# car_in.net
KiCad netlist of a schematic drawn in Altium Designer
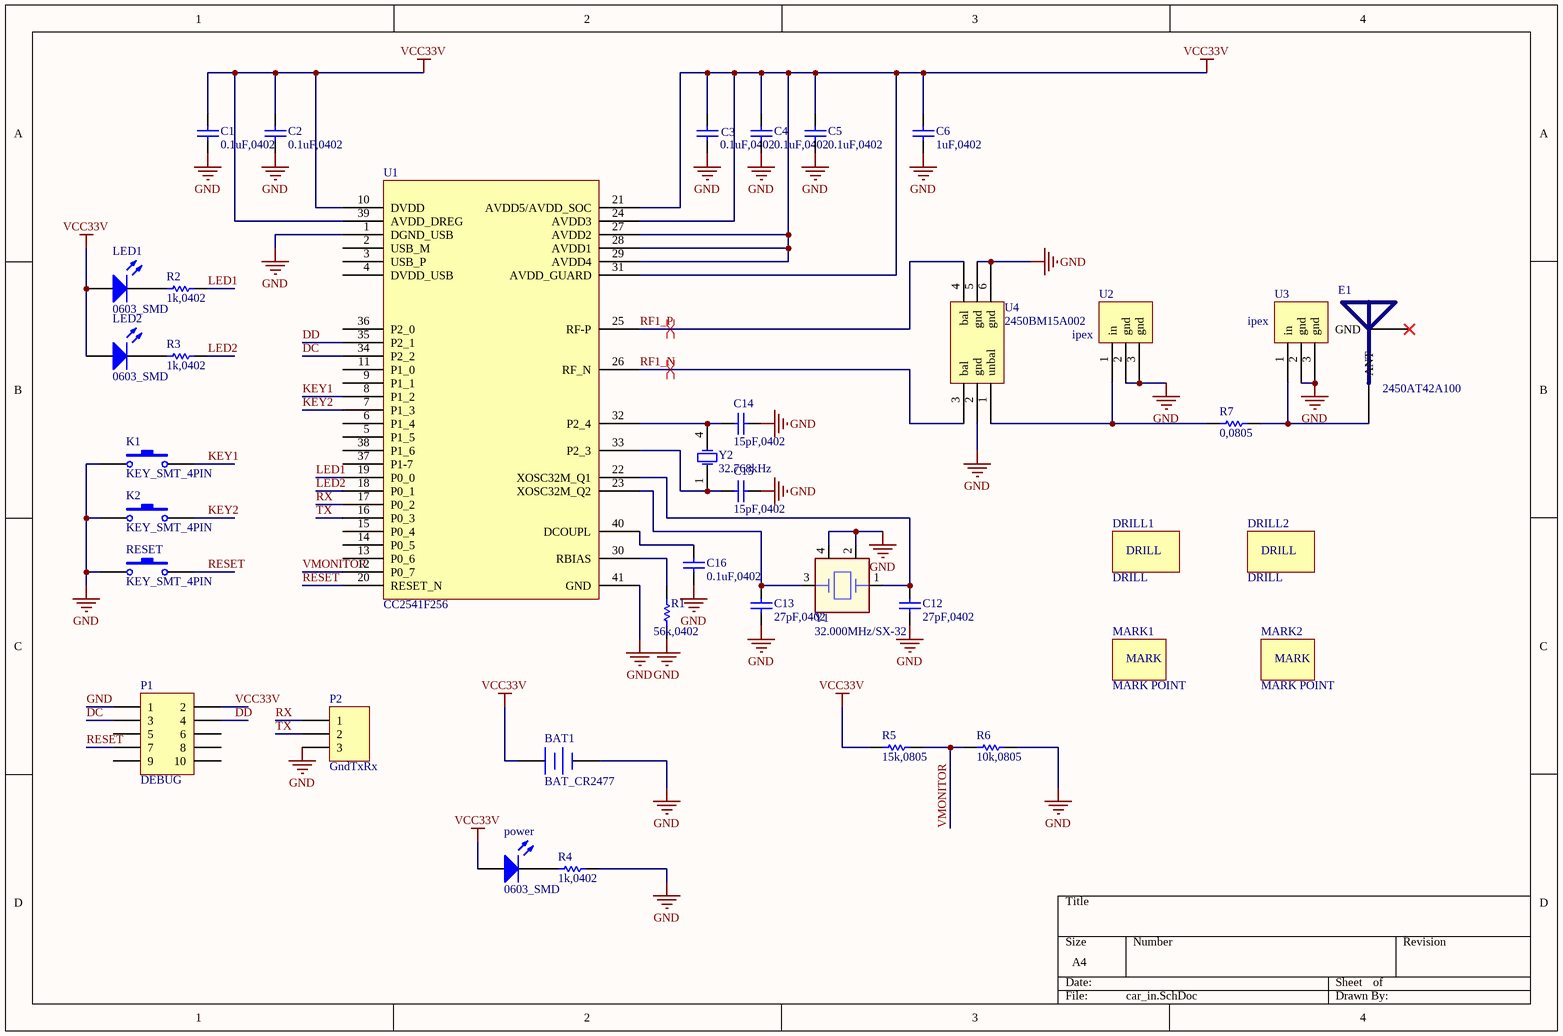
[diagram p0: car_in.SchDoc]

(export (version "E")
  (design (tool "Eeschema 10.0.6"))
  (components
    (comp (ref "BAT1")
      (value "BAT_CR2477")
      (footprint "CR2477")
      (description "battery")
      (libsource (lib "Inte") (part "BAT"))
    )
    (comp (ref "C1")
      (value "0.1uF,0402")
      (footprint "C0402")
      (description "Capacitor")
      (fields (field (name "PUBLISHER") "Altium Limited"))
      (libsource (lib "Inte") (part "CAP"))
    )
    (comp (ref "C2")
      (value "0.1uF,0402")
      (footprint "C0402")
      (description "Capacitor")
      (fields (field (name "PUBLISHER") "Altium Limited"))
      (libsource (lib "Inte") (part "CAP"))
    )
    (comp (ref "C3")
      (value "0.1uF,0402")
      (footprint "C0402")
      (description "Capacitor")
      (fields (field (name "PUBLISHER") "Altium Limited"))
      (libsource (lib "Inte") (part "CAP"))
    )
    (comp (ref "C4")
      (value "0.1uF,0402")
      (footprint "C0402")
      (description "Capacitor")
      (fields (field (name "PUBLISHER") "Altium Limited"))
      (libsource (lib "Inte") (part "CAP"))
    )
    (comp (ref "C5")
      (value "0.1uF,0402")
      (footprint "C0402")
      (description "Capacitor")
      (fields (field (name "PUBLISHER") "Altium Limited"))
      (libsource (lib "Inte") (part "CAP"))
    )
    (comp (ref "C6")
      (value "1uF,0402")
      (footprint "C0402")
      (description "Capacitor")
      (fields (field (name "PUBLISHER") "Altium Limited"))
      (libsource (lib "Inte") (part "CAP"))
    )
    (comp (ref "C12")
      (value "27pF,0402")
      (footprint "C0402")
      (description "Capacitor")
      (fields (field (name "PUBLISHER") "Altium Limited"))
      (libsource (lib "Inte") (part "CAP"))
    )
    (comp (ref "C13")
      (value "27pF,0402")
      (footprint "C0402")
      (description "Capacitor")
      (fields (field (name "PUBLISHER") "Altium Limited"))
      (libsource (lib "Inte") (part "CAP"))
    )
    (comp (ref "C14")
      (value "15pF,0402")
      (footprint "C0402")
      (description "Capacitor")
      (fields (field (name "PUBLISHER") "Altium Limited"))
      (libsource (lib "Inte") (part "CAP"))
    )
    (comp (ref "C15")
      (value "15pF,0402")
      (footprint "C0402")
      (description "Capacitor")
      (fields (field (name "PUBLISHER") "Altium Limited"))
      (libsource (lib "Inte") (part "CAP"))
    )
    (comp (ref "C16")
      (value "0.1uF,0402")
      (footprint "C0402")
      (description "Capacitor")
      (fields (field (name "PUBLISHER") "Altium Limited"))
      (libsource (lib "Inte") (part "CAP"))
    )
    (comp (ref "DRILL1") (value "DRILL") (footprint "DRILL_2MM") (libsource (lib "Inte") (part "DRILL")))
    (comp (ref "DRILL2") (value "DRILL") (footprint "DRILL_2MM") (libsource (lib "Inte") (part "DRILL")))
    (comp (ref "E1")
      (value "2450AT42A100")
      (footprint "BT_ANT_PCB")
      (libsource (lib "Inte") (part "BT_ANT_PCB"))
    )
    (comp (ref "K1") (value "KEY_SMT_4PIN") (footprint "KEY-SMT") (libsource (lib "Inte") (part "KEY")))
    (comp (ref "K2") (value "KEY_SMT_4PIN") (footprint "KEY-SMT") (libsource (lib "Inte") (part "KEY")))
    (comp (ref "LED1")
      (value "0603_SMD")
      (footprint "LED0603")
      (description "led")
      (libsource (lib "Inte") (part "LED"))
    )
    (comp (ref "LED2")
      (value "0603_SMD")
      (footprint "LED0603")
      (description "led")
      (libsource (lib "Inte") (part "LED"))
    )
    (comp (ref "MARK1")
      (value "MARK POINT")
      (footprint "MARK_POINT")
      (libsource (lib "Inte") (part "MARK_POINT"))
    )
    (comp (ref "MARK2")
      (value "MARK POINT")
      (footprint "MARK_POINT")
      (libsource (lib "Inte") (part "MARK_POINT"))
    )
    (comp (ref "P1")
      (value "DEBUG")
      (footprint "HDR2X5")
      (description "Header, 5-Pin, Dual row")
      (fields (field (name "PUBLISHER") "Altium Limited"))
      (libsource (lib "Inte") (part "Header 5X2"))
    )
    (comp (ref "P2")
      (value "GndTxRx")
      (footprint "HDR1X3")
      (description "Header, 3-Pin")
      (fields (field (name "PUBLISHER") "Altium Limited"))
      (libsource (lib "Miscellaneous Connectors") (part "Header 3"))
    )
    (comp (ref "power")
      (value "0603_SMD")
      (footprint "LED0603")
      (description "led")
      (libsource (lib "Inte") (part "LED"))
    )
    (comp (ref "R1")
      (value "56k,0402")
      (footprint "R0402")
      (description "Resistor")
      (fields (field (name "PUBLISHER") "Altium Limited"))
      (libsource (lib "Inte") (part "Res1"))
    )
    (comp (ref "R2")
      (value "1k,0402")
      (footprint "R0402")
      (description "Resistor")
      (fields (field (name "PUBLISHER") "Altium Limited"))
      (libsource (lib "Inte") (part "Res1"))
    )
    (comp (ref "R3")
      (value "1k,0402")
      (footprint "R0402")
      (description "Resistor")
      (fields (field (name "PUBLISHER") "Altium Limited"))
      (libsource (lib "Inte") (part "Res1"))
    )
    (comp (ref "R4")
      (value "1k,0402")
      (footprint "R0402")
      (description "Resistor")
      (fields (field (name "PUBLISHER") "Altium Limited"))
      (libsource (lib "Inte") (part "Res1"))
    )
    (comp (ref "R5")
      (value "15k,0805")
      (footprint "R0805")
      (description "Resistor")
      (fields (field (name "PUBLISHER") "Altium Limited"))
      (libsource (lib "Inte") (part "Res1"))
    )
    (comp (ref "R6")
      (value "10k,0805")
      (footprint "R0805")
      (description "Resistor")
      (fields (field (name "PUBLISHER") "Altium Limited"))
      (libsource (lib "Inte") (part "Res1"))
    )
    (comp (ref "R7")
      (value "0,0805")
      (footprint "R0805")
      (description "Resistor")
      (fields (field (name "PUBLISHER") "Altium Limited"))
      (libsource (lib "Inte") (part "Res1"))
    )
    (comp (ref "RESET") (value "KEY_SMT_4PIN") (footprint "KEY-SMT") (libsource (lib "Inte") (part "KEY")))
    (comp (ref "U1")
      (value "CC2541F256")
      (footprint "PQFP40")
      (description "TI cc2541F256")
      (libsource (lib "Inte") (part "CC254x"))
    )
    (comp (ref "U2") (value "ipex") (footprint "IPEX") (libsource (lib "Inte") (part "IPEX")))
    (comp (ref "U3") (value "ipex") (footprint "IPEX") (libsource (lib "Inte") (part "IPEX")))
    (comp (ref "U4")
      (value "2450BM15A002")
      (footprint "2450BM15A002")
      (libsource (lib "Inte") (part "2450BM15A002"))
    )
    (comp (ref "Y1")
      (value "32.000MHz/SX-32")
      (footprint "1210")
      (description "SPXO")
      (libsource (lib "Inte") (part "CRYSTAL_5"))
    )
    (comp (ref "Y2")
      (value "32.768kHz")
      (footprint "1206")
      (description "crystal")
      (libsource (lib "Inte") (part "DA740C"))
    )
  )
  (nets
    (net (code "1") (name "/DC") (class "Default")
      (node (ref "P1") (pin "3") (pinfunction "3_3") (pintype "passive"))
      (node (ref "U1") (pin "34") (pinfunction "P2_2_34") (pintype "passive"))
    )
    (net (code "2") (name "/DD") (class "Default")
      (node (ref "P1") (pin "4") (pinfunction "4_4") (pintype "passive"))
      (node (ref "U1") (pin "35") (pinfunction "P2_1_35") (pintype "passive"))
    )
    (net (code "3") (name "/KEY1") (class "Default")
      (node (ref "K1") (pin "2") (pinfunction "2_2") (pintype "passive"))
      (node (ref "U1") (pin "8") (pinfunction "P1_2_8") (pintype "passive"))
    )
    (net (code "4") (name "/KEY2") (class "Default")
      (node (ref "K2") (pin "2") (pinfunction "2_2") (pintype "passive"))
      (node (ref "U1") (pin "7") (pinfunction "P1_3_7") (pintype "passive"))
    )
    (net (code "5") (name "/LED1") (class "Default")
      (node (ref "R2") (pin "2") (pinfunction "2_2") (pintype "passive"))
      (node (ref "U1") (pin "19") (pinfunction "P0_0_19") (pintype "passive"))
    )
    (net (code "6") (name "/LED2") (class "Default")
      (node (ref "R3") (pin "2") (pinfunction "2_2") (pintype "passive"))
      (node (ref "U1") (pin "18") (pinfunction "P0_1_18") (pintype "passive"))
    )
    (net (code "7") (name "/RESET") (class "Default")
      (node (ref "P1") (pin "7") (pinfunction "7_7") (pintype "passive"))
      (node (ref "RESET") (pin "2") (pinfunction "2_2") (pintype "passive"))
      (node (ref "U1") (pin "20") (pinfunction "RESET_N_20") (pintype "passive"))
    )
    (net (code "8") (name "/RF1_N") (class "Default")
      (node (ref "U1") (pin "26") (pinfunction "RF_N_26") (pintype "passive"))
      (node (ref "U4") (pin "3") (pinfunction "bal_3") (pintype "passive"))
    )
    (net (code "9") (name "/RF1_P") (class "Default")
      (node (ref "U1") (pin "25") (pinfunction "RF-P_25") (pintype "passive"))
      (node (ref "U4") (pin "4") (pinfunction "bal_4") (pintype "passive"))
    )
    (net (code "10") (name "/RX") (class "Default")
      (node (ref "P2") (pin "1") (pinfunction "1_1") (pintype "passive"))
      (node (ref "U1") (pin "17") (pinfunction "P0_2_17") (pintype "passive"))
    )
    (net (code "11") (name "/TX") (class "Default")
      (node (ref "P2") (pin "2") (pinfunction "2_2") (pintype "passive"))
      (node (ref "U1") (pin "16") (pinfunction "P0_3_16") (pintype "passive"))
    )
    (net (code "12") (name "/VMONITOR") (class "Default")
      (node (ref "R5") (pin "2") (pinfunction "2_2") (pintype "passive"))
      (node (ref "R6") (pin "1") (pinfunction "1_1") (pintype "passive"))
      (node (ref "U1") (pin "12") (pinfunction "P0_7_12") (pintype "passive"))
    )
    (net (code "13") (name "GND") (class "Default")
      (node (ref "BAT1") (pin "2") (pinfunction "-_2") (pintype "passive"))
      (node (ref "C1") (pin "1") (pinfunction "1_1") (pintype "passive"))
      (node (ref "C12") (pin "1") (pinfunction "1_1") (pintype "passive"))
      (node (ref "C13") (pin "1") (pinfunction "1_1") (pintype "passive"))
      (node (ref "C14") (pin "2") (pinfunction "2_2") (pintype "passive"))
      (node (ref "C15") (pin "2") (pinfunction "2_2") (pintype "passive"))
      (node (ref "C16") (pin "1") (pinfunction "1_1") (pintype "passive"))
      (node (ref "C2") (pin "1") (pinfunction "1_1") (pintype "passive"))
      (node (ref "C3") (pin "2") (pinfunction "2_2") (pintype "passive"))
      (node (ref "C4") (pin "1") (pinfunction "1_1") (pintype "passive"))
      (node (ref "C5") (pin "1") (pinfunction "1_1") (pintype "passive"))
      (node (ref "C6") (pin "1") (pinfunction "1_1") (pintype "passive"))
      (node (ref "K1") (pin "1") (pinfunction "1_1") (pintype "passive"))
      (node (ref "K2") (pin "1") (pinfunction "1_1") (pintype "passive"))
      (node (ref "P1") (pin "1") (pinfunction "1_1") (pintype "passive"))
      (node (ref "P2") (pin "3") (pinfunction "3_3") (pintype "passive"))
      (node (ref "R1") (pin "1") (pinfunction "1_1") (pintype "passive"))
      (node (ref "R4") (pin "2") (pinfunction "2_2") (pintype "passive"))
      (node (ref "R6") (pin "2") (pinfunction "2_2") (pintype "passive"))
      (node (ref "RESET") (pin "1") (pinfunction "1_1") (pintype "passive"))
      (node (ref "U1") (pin "1") (pinfunction "DGND_USB_1") (pintype "passive"))
      (node (ref "U1") (pin "41") (pinfunction "GND_41") (pintype "passive"))
      (node (ref "U2") (pin "2") (pinfunction "gnd_2") (pintype "passive"))
      (node (ref "U2") (pin "3") (pinfunction "gnd_3") (pintype "passive"))
      (node (ref "U3") (pin "2") (pinfunction "gnd_2") (pintype "passive"))
      (node (ref "U3") (pin "3") (pinfunction "gnd_3") (pintype "passive"))
      (node (ref "U4") (pin "2") (pinfunction "gnd_2") (pintype "passive"))
      (node (ref "U4") (pin "5") (pinfunction "gnd_5") (pintype "passive"))
      (node (ref "U4") (pin "6") (pinfunction "gnd_6") (pintype "passive"))
      (node (ref "Y1") (pin "2") (pinfunction "2_2") (pintype "passive"))
      (node (ref "Y1") (pin "4") (pinfunction "4_4") (pintype "passive"))
    )
    (net (code "14") (name "Net-(E1-ANT)") (class "Default")
      (node (ref "E1") (pin "1") (pinfunction "ANT_1") (pintype "passive"))
      (node (ref "R7") (pin "2") (pinfunction "2_2") (pintype "passive"))
      (node (ref "U3") (pin "1") (pinfunction "in_1") (pintype "passive"))
    )
    (net (code "15") (name "Net-(LED1-K)") (class "Default")
      (node (ref "LED1") (pin "2") (pinfunction "K_2") (pintype "passive"))
      (node (ref "R2") (pin "1") (pinfunction "1_1") (pintype "passive"))
    )
    (net (code "16") (name "Net-(LED2-K)") (class "Default")
      (node (ref "LED2") (pin "2") (pinfunction "K_2") (pintype "passive"))
      (node (ref "R3") (pin "1") (pinfunction "1_1") (pintype "passive"))
    )
    (net (code "17") (name "Net-(U1-DCOUPL)") (class "Default")
      (node (ref "C16") (pin "2") (pinfunction "2_2") (pintype "passive"))
      (node (ref "U1") (pin "40") (pinfunction "DCOUPL_40") (pintype "passive"))
    )
    (net (code "18") (name "Net-(U1-P2_3)") (class "Default")
      (node (ref "C15") (pin "1") (pinfunction "1_1") (pintype "passive"))
      (node (ref "U1") (pin "33") (pinfunction "P2_3_33") (pintype "passive"))
      (node (ref "Y2") (pin "1") (pinfunction "OSC1_1") (pintype "passive"))
    )
    (net (code "19") (name "Net-(U1-P2_4)") (class "Default")
      (node (ref "C14") (pin "1") (pinfunction "1_1") (pintype "passive"))
      (node (ref "U1") (pin "32") (pinfunction "P2_4_32") (pintype "passive"))
      (node (ref "Y2") (pin "4") (pinfunction "OSC2_4") (pintype "passive"))
    )
    (net (code "20") (name "Net-(U1-RBIAS)") (class "Default")
      (node (ref "R1") (pin "2") (pinfunction "2_2") (pintype "passive"))
      (node (ref "U1") (pin "30") (pinfunction "RBIAS_30") (pintype "passive"))
    )
    (net (code "21") (name "Net-(U1-XOSC32M_Q1)") (class "Default")
      (node (ref "C12") (pin "2") (pinfunction "2_2") (pintype "passive"))
      (node (ref "U1") (pin "22") (pinfunction "XOSC32M_Q1_22") (pintype "passive"))
      (node (ref "Y1") (pin "1") (pinfunction "1_1") (pintype "passive"))
    )
    (net (code "22") (name "Net-(U1-XOSC32M_Q2)") (class "Default")
      (node (ref "C13") (pin "2") (pinfunction "2_2") (pintype "passive"))
      (node (ref "U1") (pin "23") (pinfunction "XOSC32M_Q2_23") (pintype "passive"))
      (node (ref "Y1") (pin "3") (pinfunction "3_3") (pintype "passive"))
    )
    (net (code "23") (name "Net-(U2-in)") (class "Default")
      (node (ref "R7") (pin "1") (pinfunction "1_1") (pintype "passive"))
      (node (ref "U2") (pin "1") (pinfunction "in_1") (pintype "passive"))
      (node (ref "U4") (pin "1") (pinfunction "unbal_1") (pintype "passive"))
    )
    (net (code "24") (name "Net-(power-K)") (class "Default")
      (node (ref "R4") (pin "1") (pinfunction "1_1") (pintype "passive"))
      (node (ref "power") (pin "2") (pinfunction "K_2") (pintype "passive"))
    )
    (net (code "25") (name "VCC33V") (class "Default")
      (node (ref "BAT1") (pin "1") (pinfunction "+_1") (pintype "passive"))
      (node (ref "C1") (pin "2") (pinfunction "2_2") (pintype "passive"))
      (node (ref "C2") (pin "2") (pinfunction "2_2") (pintype "passive"))
      (node (ref "C3") (pin "1") (pinfunction "1_1") (pintype "passive"))
      (node (ref "C4") (pin "2") (pinfunction "2_2") (pintype "passive"))
      (node (ref "C5") (pin "2") (pinfunction "2_2") (pintype "passive"))
      (node (ref "C6") (pin "2") (pinfunction "2_2") (pintype "passive"))
      (node (ref "LED1") (pin "1") (pinfunction "A_1") (pintype "passive"))
      (node (ref "LED2") (pin "1") (pinfunction "A_1") (pintype "passive"))
      (node (ref "P1") (pin "2") (pinfunction "2_2") (pintype "passive"))
      (node (ref "R5") (pin "1") (pinfunction "1_1") (pintype "passive"))
      (node (ref "U1") (pin "10") (pinfunction "DVDD_10") (pintype "passive"))
      (node (ref "U1") (pin "21") (pinfunction "AVDD5/AVDD_SOC_21") (pintype "passive"))
      (node (ref "U1") (pin "24") (pinfunction "AVDD3_24") (pintype "passive"))
      (node (ref "U1") (pin "27") (pinfunction "AVDD2_27") (pintype "passive"))
      (node (ref "U1") (pin "28") (pinfunction "AVDD1_28") (pintype "passive"))
      (node (ref "U1") (pin "29") (pinfunction "AVDD4_29") (pintype "passive"))
      (node (ref "U1") (pin "31") (pinfunction "AVDD_GUARD_31") (pintype "passive"))
      (node (ref "U1") (pin "39") (pinfunction "AVDD_DREG_39") (pintype "passive"))
      (node (ref "power") (pin "1") (pinfunction "A_1") (pintype "passive"))
    )
    (net (code "26") (name "unconnected-(E1-GND-Pad2)") (class "Default")
      (node (ref "E1") (pin "2") (pinfunction "GND_2") (pintype "passive+no_connect"))
    )
    (net (code "27") (name "unconnected-(P1-Pad5)") (class "Default")
      (node (ref "P1") (pin "5") (pinfunction "5_5") (pintype "passive"))
    )
    (net (code "28") (name "unconnected-(P1-Pad6)") (class "Default")
      (node (ref "P1") (pin "6") (pinfunction "6_6") (pintype "passive"))
    )
    (net (code "29") (name "unconnected-(P1-Pad8)") (class "Default")
      (node (ref "P1") (pin "8") (pinfunction "8_8") (pintype "passive"))
    )
    (net (code "30") (name "unconnected-(P1-Pad9)") (class "Default")
      (node (ref "P1") (pin "9") (pinfunction "9_9") (pintype "passive"))
    )
    (net (code "31") (name "unconnected-(P1-Pad10)") (class "Default")
      (node (ref "P1") (pin "10") (pinfunction "10_10") (pintype "passive"))
    )
    (net (code "32") (name "unconnected-(U1-DVDD_USB-Pad4)") (class "Default")
      (node (ref "U1") (pin "4") (pinfunction "DVDD_USB_4") (pintype "passive"))
    )
    (net (code "33") (name "unconnected-(U1-P0_4-Pad15)") (class "Default")
      (node (ref "U1") (pin "15") (pinfunction "P0_4_15") (pintype "passive"))
    )
    (net (code "34") (name "unconnected-(U1-P0_5-Pad14)") (class "Default")
      (node (ref "U1") (pin "14") (pinfunction "P0_5_14") (pintype "passive"))
    )
    (net (code "35") (name "unconnected-(U1-P0_6-Pad13)") (class "Default")
      (node (ref "U1") (pin "13") (pinfunction "P0_6_13") (pintype "passive"))
    )
    (net (code "36") (name "unconnected-(U1-P1-7-Pad37)") (class "Default")
      (node (ref "U1") (pin "37") (pinfunction "P1-7_37") (pintype "passive"))
    )
    (net (code "37") (name "unconnected-(U1-P1_0-Pad11)") (class "Default")
      (node (ref "U1") (pin "11") (pinfunction "P1_0_11") (pintype "passive"))
    )
    (net (code "38") (name "unconnected-(U1-P1_1-Pad9)") (class "Default")
      (node (ref "U1") (pin "9") (pinfunction "P1_1_9") (pintype "passive"))
    )
    (net (code "39") (name "unconnected-(U1-P1_4-Pad6)") (class "Default")
      (node (ref "U1") (pin "6") (pinfunction "P1_4_6") (pintype "passive"))
    )
    (net (code "40") (name "unconnected-(U1-P1_5-Pad5)") (class "Default")
      (node (ref "U1") (pin "5") (pinfunction "P1_5_5") (pintype "passive"))
    )
    (net (code "41") (name "unconnected-(U1-P1_6-Pad38)") (class "Default")
      (node (ref "U1") (pin "38") (pinfunction "P1_6_38") (pintype "passive"))
    )
    (net (code "42") (name "unconnected-(U1-P2_0-Pad36)") (class "Default")
      (node (ref "U1") (pin "36") (pinfunction "P2_0_36") (pintype "passive"))
    )
    (net (code "43") (name "unconnected-(U1-USB_M-Pad2)") (class "Default")
      (node (ref "U1") (pin "2") (pinfunction "USB_M_2") (pintype "passive"))
    )
    (net (code "44") (name "unconnected-(U1-USB_P-Pad3)") (class "Default")
      (node (ref "U1") (pin "3") (pinfunction "USB_P_3") (pintype "passive"))
    )
  )
)
